# 4ch_GRT_reader_v6.net
KiCad netlist of a schematic drawn in Altium Designer
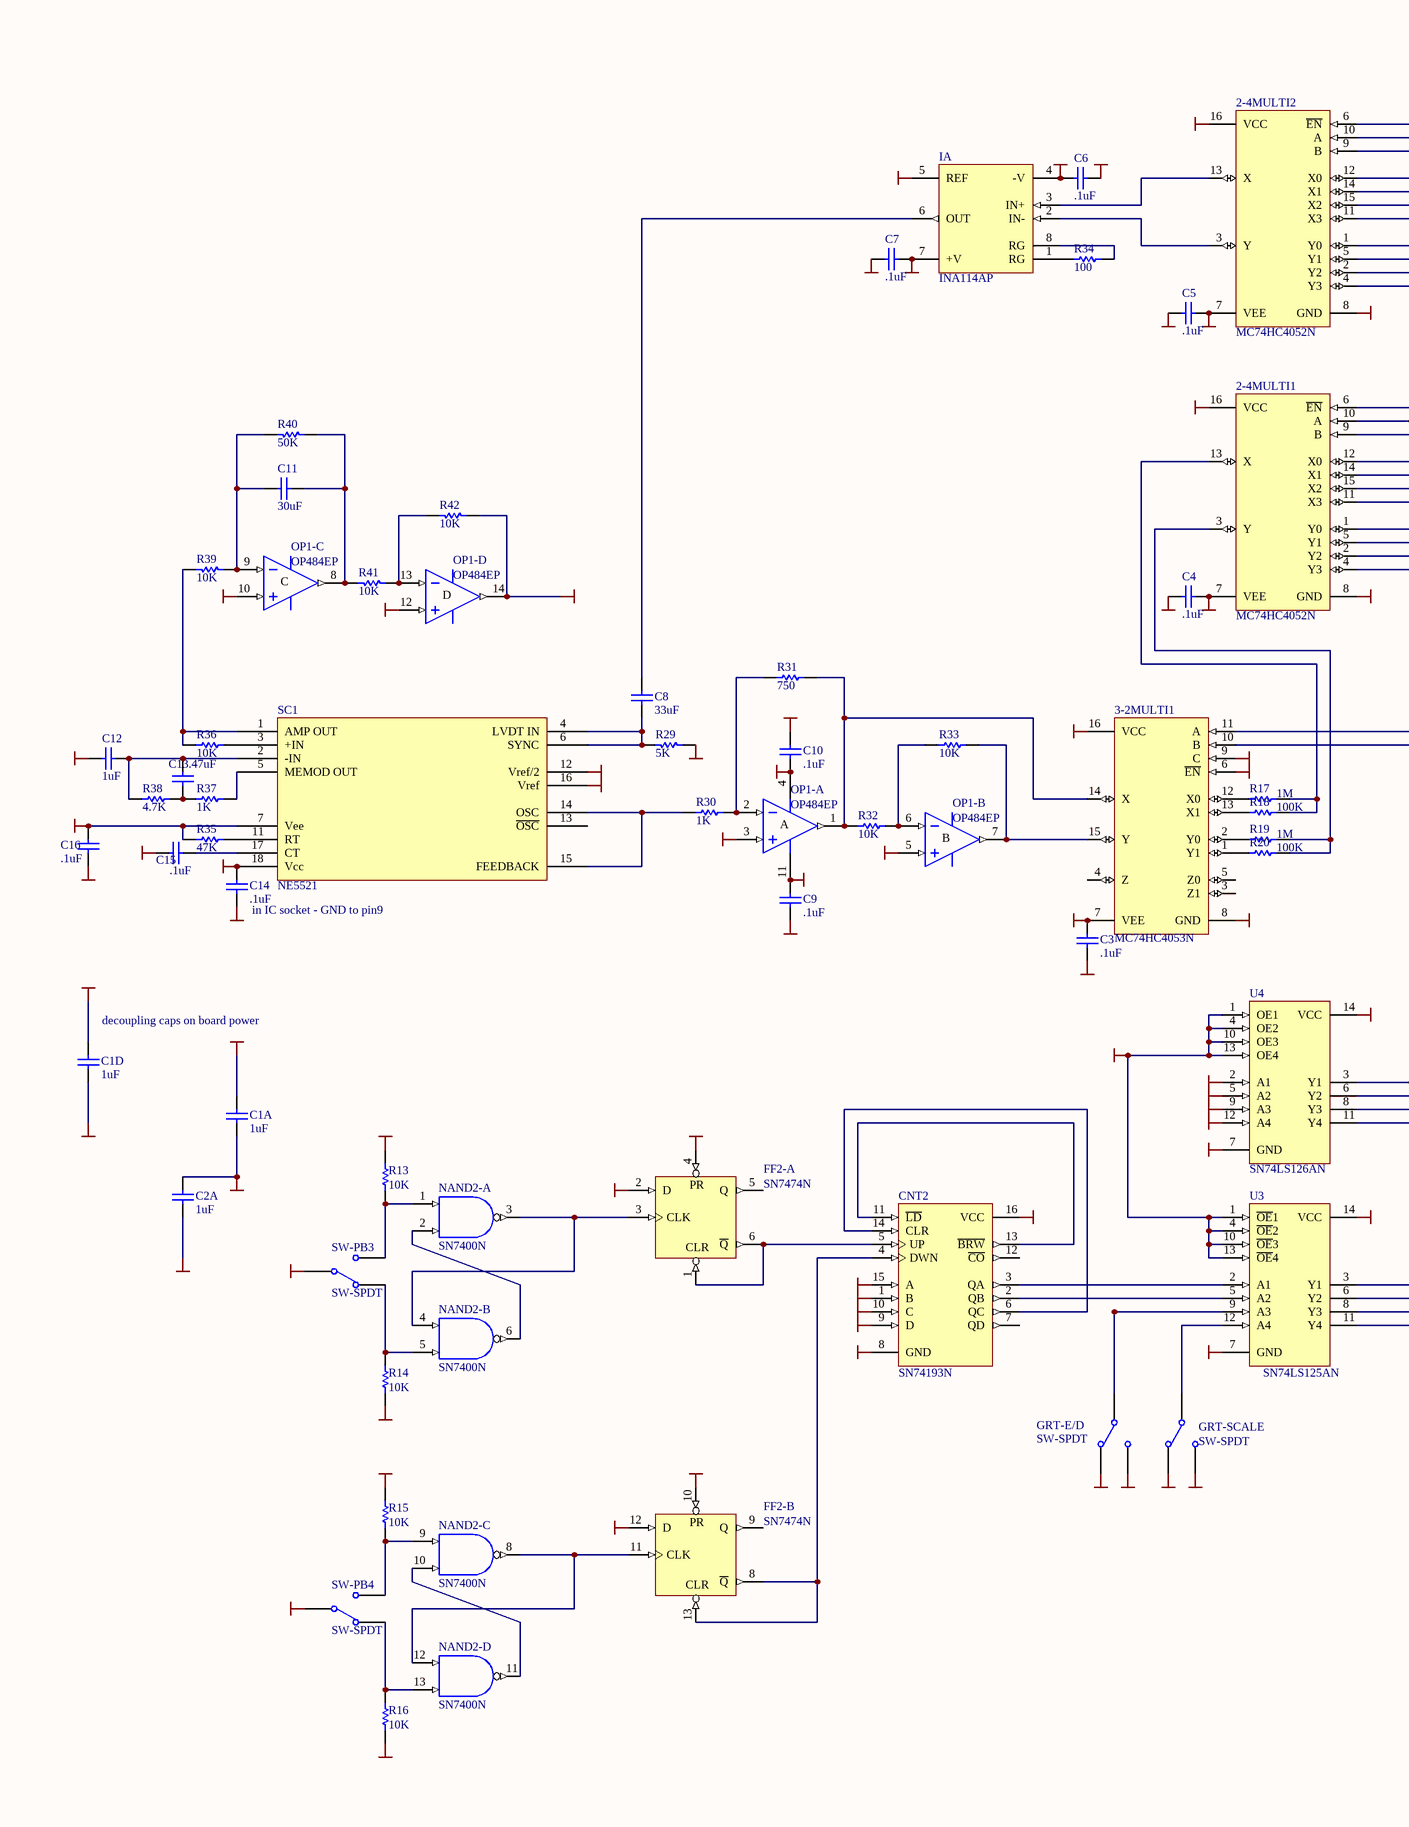
[diagram p0: 4ch GRT reader v6.SCHDOC, left]
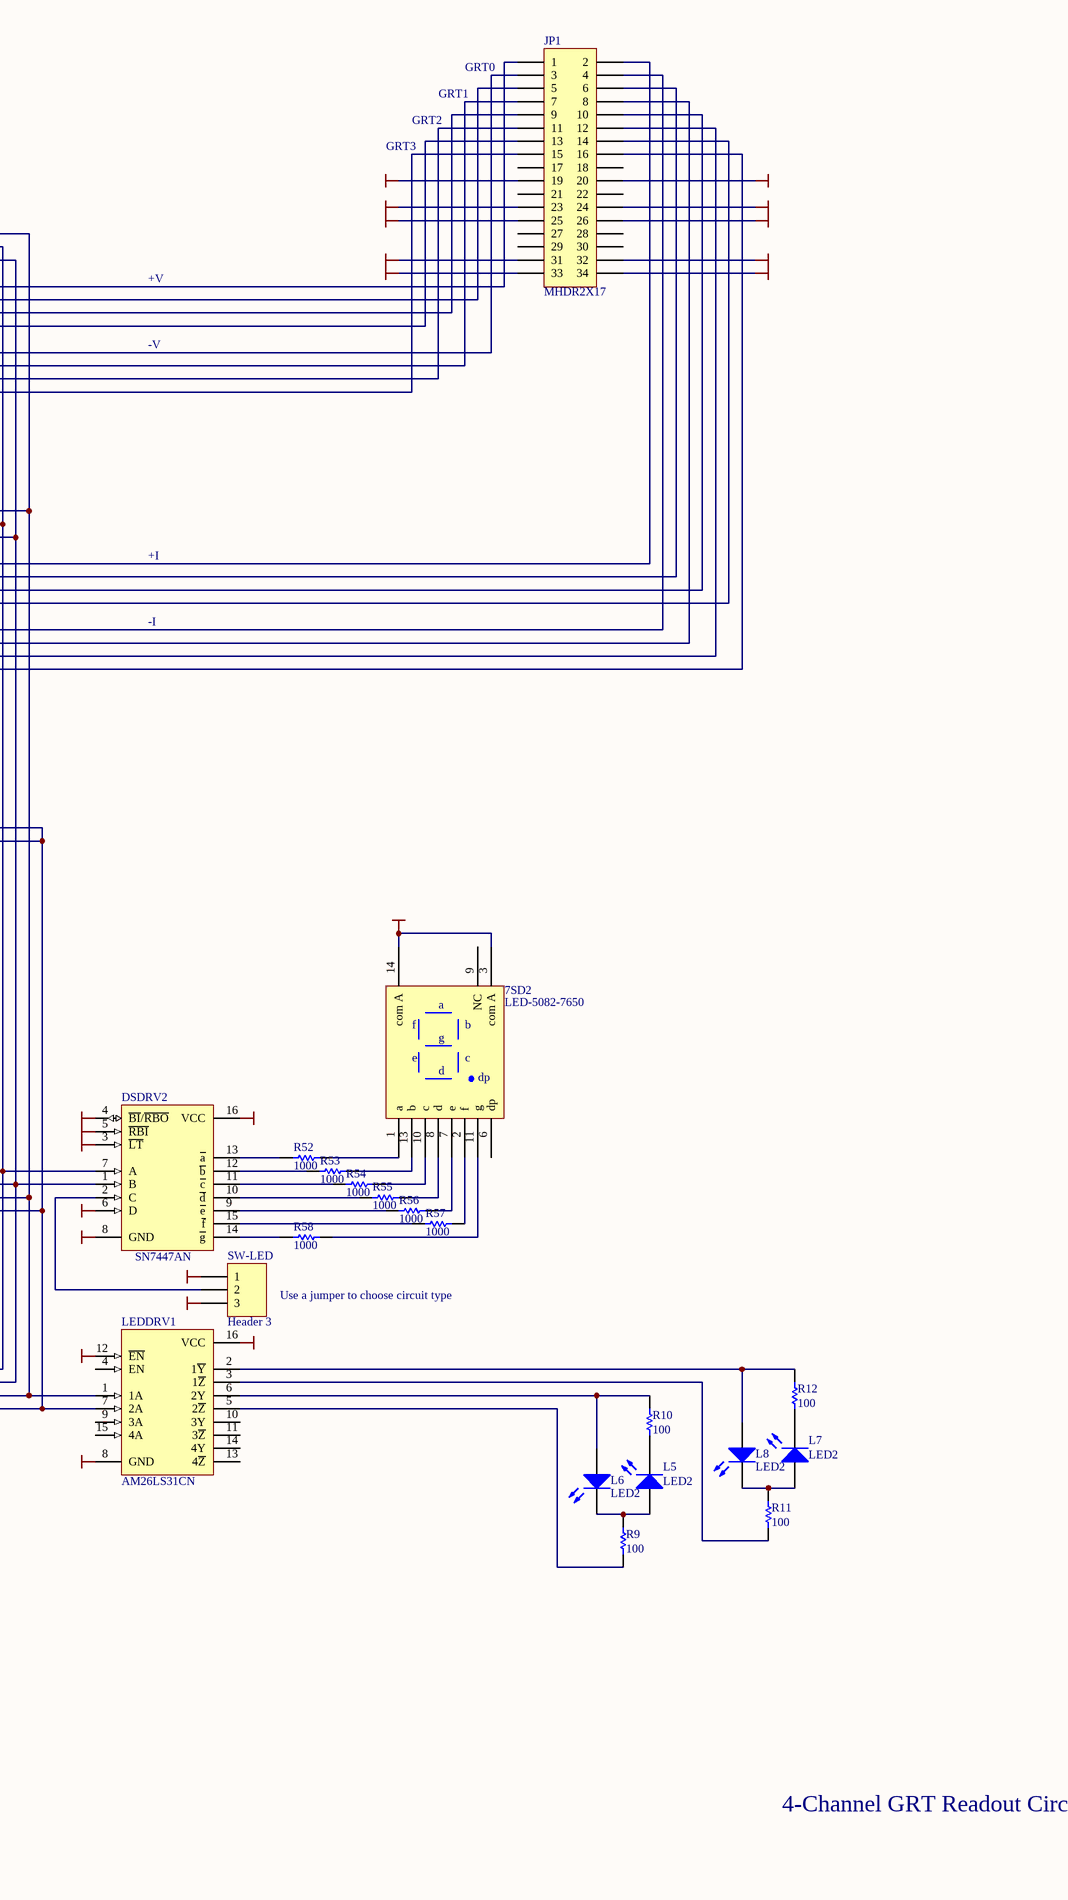
[diagram p1: 4ch GRT reader v6.SCHDOC, right]

(export (version "E")
  (design (tool "Eeschema 10.0.6"))
  (components
    (comp (ref "2-4MULTI1")
      (value "MC74HC4052N")
      (footprint "DIP-16/X1.5")
      (description "Dual 4-Channel Analog Multiplexer/Demultiplexer")
      (fields (field (name "MANUFACTURER") "ON Semiconductor") (field (name "PUBLISHER") "Altium Limited"))
      (libsource (lib "ON Semi Logic Multiplexer") (part "MC74HC4052N"))
    )
    (comp (ref "2-4MULTI2")
      (value "MC74HC4052N")
      (footprint "DIP-16/X1.5")
      (description "Dual 4-Channel Analog Multiplexer/Demultiplexer")
      (fields (field (name "MANUFACTURER") "ON Semiconductor") (field (name "PUBLISHER") "Altium Limited"))
      (libsource (lib "ON Semi Logic Multiplexer") (part "MC74HC4052N"))
    )
    (comp (ref "3-2MULTI1")
      (value "MC74HC4053N")
      (footprint "DIP-16/X1.5")
      (description "Analog Multiplexer/Demultiplexer")
      (fields (field (name "MANUFACTURER") "ON Semiconductor") (field (name "PUBLISHER") "Altium Limited"))
      (libsource (lib "ON Semi Logic Multiplexer") (part "MC74HC4053N"))
    )
    (comp (ref "7SD2")
      (value "LED-5082-7650")
      (footprint "DIP-14")
      (libsource (lib "Steves Integrated Library1") (part "LED-5082-7650"))
    )
    (comp (ref "C1A")
      (value "1uF")
      (footprint "RAD-0.2")
      (description "Capacitor")
      (fields
        (field (name "MANUFACTURER") "Generic Components")
        (field (name "ALTIUM_VALUE") "1uF")
        (field (name "PUBLISHER") "Altium Limited")
      )
      (libsource (lib "Miscellaneous Devices") (part "Cap"))
    )
    (comp (ref "C1D")
      (value "1uF")
      (footprint "RAD-0.2")
      (description "Capacitor")
      (fields
        (field (name "MANUFACTURER") "Generic Components")
        (field (name "ALTIUM_VALUE") "1uF")
        (field (name "PUBLISHER") "Altium Limited")
      )
      (libsource (lib "Miscellaneous Devices") (part "Cap"))
    )
    (comp (ref "C2A")
      (value "1uF")
      (footprint "RAD-0.2")
      (description "Capacitor")
      (fields
        (field (name "MANUFACTURER") "Generic Components")
        (field (name "ALTIUM_VALUE") "1uF")
        (field (name "PUBLISHER") "Altium Limited")
      )
      (libsource (lib "Miscellaneous Devices") (part "Cap"))
    )
    (comp (ref "C3")
      (value ".1uF")
      (footprint "RAD-0.1")
      (description "Capacitor")
      (fields
        (field (name "MANUFACTURER") "Generic Components")
        (field (name "ALTIUM_VALUE") ".1uF")
        (field (name "PUBLISHER") "Altium Limited")
      )
      (libsource (lib "Miscellaneous Devices") (part "Cap"))
    )
    (comp (ref "C4")
      (value ".1uF")
      (footprint "RAD-0.1")
      (description "Capacitor")
      (fields
        (field (name "MANUFACTURER") "Generic Components")
        (field (name "ALTIUM_VALUE") ".1uF")
        (field (name "PUBLISHER") "Altium Limited")
      )
      (libsource (lib "Miscellaneous Devices") (part "Cap"))
    )
    (comp (ref "C5")
      (value ".1uF")
      (footprint "RAD-0.1")
      (description "Capacitor")
      (fields
        (field (name "MANUFACTURER") "Generic Components")
        (field (name "ALTIUM_VALUE") ".1uF")
        (field (name "PUBLISHER") "Altium Limited")
      )
      (libsource (lib "Miscellaneous Devices") (part "Cap"))
    )
    (comp (ref "C6")
      (value ".1uF")
      (footprint "RAD-0.1")
      (description "Capacitor")
      (fields
        (field (name "MANUFACTURER") "Generic Components")
        (field (name "ALTIUM_VALUE") ".1uF")
        (field (name "PUBLISHER") "Altium Limited")
      )
      (libsource (lib "Miscellaneous Devices") (part "Cap"))
    )
    (comp (ref "C7")
      (value ".1uF")
      (footprint "RAD-0.1")
      (description "Capacitor")
      (fields
        (field (name "MANUFACTURER") "Generic Components")
        (field (name "ALTIUM_VALUE") ".1uF")
        (field (name "PUBLISHER") "Altium Limited")
      )
      (libsource (lib "Miscellaneous Devices") (part "Cap"))
    )
    (comp (ref "C8")
      (value "33uF")
      (footprint "RAD-0.1")
      (description "Capacitor")
      (fields
        (field (name "MANUFACTURER") "Generic Components")
        (field (name "ALTIUM_VALUE") "33uF")
        (field (name "PUBLISHER") "Altium Limited")
      )
      (libsource (lib "Miscellaneous Devices") (part "Cap"))
    )
    (comp (ref "C9")
      (value ".1uF")
      (footprint "RAD-0.1")
      (description "Capacitor")
      (fields
        (field (name "MANUFACTURER") "Generic Components")
        (field (name "ALTIUM_VALUE") ".1uF")
        (field (name "PUBLISHER") "Altium Limited")
      )
      (libsource (lib "Miscellaneous Devices") (part "Cap"))
    )
    (comp (ref "C10")
      (value ".1uF")
      (footprint "RAD-0.1")
      (description "Capacitor")
      (fields
        (field (name "MANUFACTURER") "Generic Components")
        (field (name "ALTIUM_VALUE") ".1uF")
        (field (name "PUBLISHER") "Altium Limited")
      )
      (libsource (lib "Miscellaneous Devices") (part "Cap"))
    )
    (comp (ref "C11")
      (value "30uF")
      (footprint "RAD-0.1")
      (description "Capacitor")
      (fields
        (field (name "MANUFACTURER") "Generic Components")
        (field (name "ALTIUM_VALUE") "30uF")
        (field (name "PUBLISHER") "Altium Limited")
      )
      (libsource (lib "Miscellaneous Devices") (part "Cap"))
    )
    (comp (ref "C12")
      (value "1uF")
      (footprint "RAD-0.1")
      (description "Capacitor")
      (fields
        (field (name "MANUFACTURER") "Generic Components")
        (field (name "ALTIUM_VALUE") "1uF")
        (field (name "PUBLISHER") "Altium Limited")
      )
      (libsource (lib "") (part "Cap_1"))
    )
    (comp (ref "C13")
      (value ".47uF")
      (footprint "RAD-0.1")
      (description "Capacitor")
      (fields
        (field (name "MANUFACTURER") "Generic Components")
        (field (name "ALTIUM_VALUE") ".47uF")
        (field (name "PUBLISHER") "Altium Limited")
      )
      (libsource (lib "Miscellaneous Devices") (part "Cap"))
    )
    (comp (ref "C14")
      (value "in IC socket - GND to pin9")
      (footprint "RAD-0.1")
      (description "Capacitor")
      (fields
        (field (name "MANUFACTURER") "Generic Components")
        (field (name "ALTIUM_VALUE") ".1uF")
        (field (name "PUBLISHER") "Altium Limited")
      )
      (libsource (lib "Miscellaneous Devices") (part "Cap"))
    )
    (comp (ref "C15")
      (value ".1uF")
      (footprint "RAD-0.1")
      (description "Capacitor")
      (fields
        (field (name "MANUFACTURER") "Generic Components")
        (field (name "ALTIUM_VALUE") ".1uF")
        (field (name "PUBLISHER") "Altium Limited")
      )
      (libsource (lib "Miscellaneous Devices") (part "Cap"))
    )
    (comp (ref "C16")
      (value ".1uF")
      (footprint "RAD-0.1")
      (description "Capacitor")
      (fields
        (field (name "MANUFACTURER") "Generic Components")
        (field (name "ALTIUM_VALUE") ".1uF")
        (field (name "PUBLISHER") "Altium Limited")
      )
      (libsource (lib "Miscellaneous Devices") (part "Cap"))
    )
    (comp (ref "CNT2")
      (value "SN74193N")
      (footprint "DIP-16/X1.5")
      (description "Synchronous 4-Bit Up/Down Counter (Dual Clock with Clear)")
      (fields (field (name "MANUFACTURER") "Texas Instruments") (field (name "PUBLISHER") "Altium Limited"))
      (libsource (lib "TI Logic Counter") (part "SN74193N"))
    )
    (comp (ref "DSDRV2")
      (value "SN7447AN")
      (footprint "DIP-16/X1.5")
      (description "BCD-to-Seven-Segment Decoder/Driver")
      (fields (field (name "MANUFACTURER") "Texas Instruments") (field (name "PUBLISHER") "Altium Limited"))
      (libsource (lib "TI Interface Display Driver") (part "SN7447AN"))
    )
    (comp (ref "FF2-")
      (value "SN7474N")
      (footprint "DIP-14/D19.7")
      (description "Dual D-Type Positive-Edge-Triggered Flip-Flop with Preset and Clear")
      (fields (field (name "MANUFACTURER") "Texas Instruments") (field (name "PUBLISHER") "Altium Limited"))
      (libsource (lib "TI Logic Flip-Flop") (part "SN7474N"))
    )
    (comp (ref "GRT-E/D")
      (value "SW-SPDT")
      (footprint "SPDT-3")
      (description "Single-Pole, Double-Throw Switch")
      (fields (field (name "MANUFACTURER") "Generic Components") (field (name "PUBLISHER") "Altium Limited"))
      (libsource (lib "Miscellaneous Devices") (part "SW-SPDT"))
    )
    (comp (ref "GRT-SCALE")
      (value "SW-SPDT")
      (footprint "SPDT-3")
      (description "Single-Pole, Double-Throw Switch")
      (fields (field (name "MANUFACTURER") "Generic Components") (field (name "PUBLISHER") "Altium Limited"))
      (libsource (lib "Miscellaneous Devices") (part "SW-SPDT"))
    )
    (comp (ref "IA")
      (value "INA114AP")
      (footprint "DIP-8")
      (description "Precision Instrumentation Amplifier")
      (fields (field (name "MANUFACTURER") "Burr-Brown") (field (name "PUBLISHER") "Altium Limited"))
      (libsource (lib "BB Instrumentation Amplifier") (part "INA114AP"))
    )
    (comp (ref "JP1")
      (value "MHDR2X17")
      (footprint "HDR2X17")
      (description "Header, 17-Pin, Dual row")
      (fields (field (name "MANUFACTURER") "Generic Components") (field (name "PUBLISHER") "Altium Limited"))
      (libsource (lib "Miscellaneous Connectors") (part "MHDR2X17"))
    )
    (comp (ref "L5")
      (value "LED2")
      (footprint "HDR1X2")
      (description "Typical RED, GREEN, YELLOW, AMBER GaAs LED")
      (fields (field (name "MANUFACTURER") "Generic Components") (field (name "PUBLISHER") "Altium Limited"))
      (libsource (lib "Miscellaneous Devices") (part "LED2"))
    )
    (comp (ref "L6")
      (value "LED2")
      (footprint "HDR1X2")
      (description "Typical RED, GREEN, YELLOW, AMBER GaAs LED")
      (fields (field (name "MANUFACTURER") "Generic Components") (field (name "PUBLISHER") "Altium Limited"))
      (libsource (lib "Miscellaneous Devices") (part "LED2"))
    )
    (comp (ref "L7")
      (value "LED2")
      (footprint "HDR1X2")
      (description "Typical RED, GREEN, YELLOW, AMBER GaAs LED")
      (fields (field (name "MANUFACTURER") "Generic Components") (field (name "PUBLISHER") "Altium Limited"))
      (libsource (lib "Miscellaneous Devices") (part "LED2"))
    )
    (comp (ref "L8")
      (value "LED2")
      (footprint "HDR1X2")
      (description "Typical RED, GREEN, YELLOW, AMBER GaAs LED")
      (fields (field (name "MANUFACTURER") "Generic Components") (field (name "PUBLISHER") "Altium Limited"))
      (libsource (lib "Miscellaneous Devices") (part "LED2"))
    )
    (comp (ref "LEDDRV1")
      (value "AM26LS31CN")
      (footprint "DIP-16/X1.5")
      (description "Quadruple Differential Line Driver")
      (fields (field (name "MANUFACTURER") "Texas Instruments") (field (name "PUBLISHER") "Altium Limited"))
      (libsource (lib "TI Interface Line Driver") (part "AM26LS31CN"))
    )
    (comp (ref "NAND2-")
      (value "SN7400N")
      (footprint "DIP-14/D19.7")
      (description "Quadruple 2-Input Positive-NAND Gate")
      (fields (field (name "MANUFACTURER") "Texas Instruments") (field (name "PUBLISHER") "Altium Limited"))
      (libsource (lib "TI Logic Gate 1") (part "SN7400N"))
    )
    (comp (ref "OP1-")
      (value "OP484EP")
      (footprint "DIP-14")
      (description "Precision Rail-to-Rail Input and Output Operational Amplifier")
      (fields (field (name "MANUFACTURER") "Analog Devices") (field (name "PUBLISHER") "Altium Limited"))
      (libsource (lib "AD Operational Amplifier") (part "OP484EP"))
    )
    (comp (ref "R9")
      (value "100")
      (footprint "AXIAL-0.3")
      (description "Resistor")
      (fields
        (field (name "MANUFACTURER") "Generic Components")
        (field (name "ALTIUM_VALUE") "100")
        (field (name "PUBLISHER") "Altium Limited")
      )
      (libsource (lib "Miscellaneous Devices") (part "Res1"))
    )
    (comp (ref "R10")
      (value "100")
      (footprint "AXIAL-0.3")
      (description "Resistor")
      (fields
        (field (name "MANUFACTURER") "Generic Components")
        (field (name "ALTIUM_VALUE") "100")
        (field (name "PUBLISHER") "Altium Limited")
      )
      (libsource (lib "Miscellaneous Devices") (part "Res1"))
    )
    (comp (ref "R11")
      (value "100")
      (footprint "AXIAL-0.3")
      (description "Resistor")
      (fields
        (field (name "MANUFACTURER") "Generic Components")
        (field (name "ALTIUM_VALUE") "100")
        (field (name "PUBLISHER") "Altium Limited")
      )
      (libsource (lib "Miscellaneous Devices") (part "Res1"))
    )
    (comp (ref "R12")
      (value "100")
      (footprint "AXIAL-0.3")
      (description "Resistor")
      (fields
        (field (name "MANUFACTURER") "Generic Components")
        (field (name "ALTIUM_VALUE") "100")
        (field (name "PUBLISHER") "Altium Limited")
      )
      (libsource (lib "Miscellaneous Devices") (part "Res1"))
    )
    (comp (ref "R13")
      (value "10K")
      (footprint "AXIAL-0.3")
      (description "Resistor")
      (fields
        (field (name "MANUFACTURER") "Generic Components")
        (field (name "ALTIUM_VALUE") "10K")
        (field (name "PUBLISHER") "Altium Limited")
      )
      (libsource (lib "Miscellaneous Devices") (part "Res1"))
    )
    (comp (ref "R14")
      (value "10K")
      (footprint "AXIAL-0.3")
      (description "Resistor")
      (fields
        (field (name "MANUFACTURER") "Generic Components")
        (field (name "ALTIUM_VALUE") "10K")
        (field (name "PUBLISHER") "Altium Limited")
      )
      (libsource (lib "Miscellaneous Devices") (part "Res1"))
    )
    (comp (ref "R15")
      (value "10K")
      (footprint "AXIAL-0.3")
      (description "Resistor")
      (fields
        (field (name "MANUFACTURER") "Generic Components")
        (field (name "ALTIUM_VALUE") "10K")
        (field (name "PUBLISHER") "Altium Limited")
      )
      (libsource (lib "Miscellaneous Devices") (part "Res1"))
    )
    (comp (ref "R16")
      (value "10K")
      (footprint "AXIAL-0.3")
      (description "Resistor")
      (fields
        (field (name "MANUFACTURER") "Generic Components")
        (field (name "ALTIUM_VALUE") "10K")
        (field (name "PUBLISHER") "Altium Limited")
      )
      (libsource (lib "Miscellaneous Devices") (part "Res1"))
    )
    (comp (ref "R17")
      (value "1M")
      (footprint "AXIAL-0.3")
      (description "Resistor")
      (fields
        (field (name "MANUFACTURER") "Generic Components")
        (field (name "ALTIUM_VALUE") "1M")
        (field (name "PUBLISHER") "Altium Limited")
      )
      (libsource (lib "Miscellaneous Devices") (part "Res1"))
    )
    (comp (ref "R18")
      (value "100K")
      (footprint "AXIAL-0.3")
      (description "Resistor")
      (fields
        (field (name "MANUFACTURER") "Generic Components")
        (field (name "ALTIUM_VALUE") "100K")
        (field (name "PUBLISHER") "Altium Limited")
      )
      (libsource (lib "Miscellaneous Devices") (part "Res1"))
    )
    (comp (ref "R19")
      (value "1M")
      (footprint "AXIAL-0.3")
      (description "Resistor")
      (fields
        (field (name "MANUFACTURER") "Generic Components")
        (field (name "ALTIUM_VALUE") "1M")
        (field (name "PUBLISHER") "Altium Limited")
      )
      (libsource (lib "Miscellaneous Devices") (part "Res1"))
    )
    (comp (ref "R20")
      (value "100K")
      (footprint "AXIAL-0.3")
      (description "Resistor")
      (fields
        (field (name "MANUFACTURER") "Generic Components")
        (field (name "ALTIUM_VALUE") "100K")
        (field (name "PUBLISHER") "Altium Limited")
      )
      (libsource (lib "Miscellaneous Devices") (part "Res1"))
    )
    (comp (ref "R29")
      (value "5K")
      (footprint "AXIAL-0.3")
      (description "Resistor")
      (fields
        (field (name "MANUFACTURER") "Generic Components")
        (field (name "ALTIUM_VALUE") "5K")
        (field (name "PUBLISHER") "Altium Limited")
      )
      (libsource (lib "") (part "Res1_2"))
    )
    (comp (ref "R30")
      (value "1K")
      (footprint "AXIAL-0.3")
      (description "Resistor")
      (fields
        (field (name "MANUFACTURER") "Generic Components")
        (field (name "ALTIUM_VALUE") "1K")
        (field (name "PUBLISHER") "Altium Limited")
      )
      (libsource (lib "Miscellaneous Devices") (part "Res1"))
    )
    (comp (ref "R31")
      (value "750")
      (footprint "AXIAL-0.3")
      (description "Resistor")
      (fields
        (field (name "MANUFACTURER") "Generic Components")
        (field (name "ALTIUM_VALUE") "750")
        (field (name "PUBLISHER") "Altium Limited")
      )
      (libsource (lib "Miscellaneous Devices") (part "Res1"))
    )
    (comp (ref "R32")
      (value "10K")
      (footprint "AXIAL-0.3")
      (description "Resistor")
      (fields
        (field (name "MANUFACTURER") "Generic Components")
        (field (name "ALTIUM_VALUE") "10K")
        (field (name "PUBLISHER") "Altium Limited")
      )
      (libsource (lib "Miscellaneous Devices") (part "Res1"))
    )
    (comp (ref "R33")
      (value "10K")
      (footprint "AXIAL-0.3")
      (description "Resistor")
      (fields
        (field (name "MANUFACTURER") "Generic Components")
        (field (name "ALTIUM_VALUE") "10K")
        (field (name "PUBLISHER") "Altium Limited")
      )
      (libsource (lib "Miscellaneous Devices") (part "Res1"))
    )
    (comp (ref "R34")
      (value "100")
      (footprint "AXIAL-0.3")
      (description "Resistor")
      (fields
        (field (name "MANUFACTURER") "Generic Components")
        (field (name "ALTIUM_VALUE") "100")
        (field (name "PUBLISHER") "Altium Limited")
      )
      (libsource (lib "Miscellaneous Devices") (part "Res1"))
    )
    (comp (ref "R35")
      (value "47K")
      (footprint "AXIAL-0.3")
      (description "Resistor")
      (fields
        (field (name "MANUFACTURER") "Generic Components")
        (field (name "ALTIUM_VALUE") "47K")
        (field (name "PUBLISHER") "Altium Limited")
      )
      (libsource (lib "Miscellaneous Devices") (part "Res1"))
    )
    (comp (ref "R36")
      (value "10K")
      (footprint "AXIAL-0.3")
      (description "Resistor")
      (fields
        (field (name "MANUFACTURER") "Generic Components")
        (field (name "ALTIUM_VALUE") "10K")
        (field (name "PUBLISHER") "Altium Limited")
      )
      (libsource (lib "") (part "Res1_1"))
    )
    (comp (ref "R37")
      (value "1K")
      (footprint "AXIAL-0.3")
      (description "Resistor")
      (fields
        (field (name "MANUFACTURER") "Generic Components")
        (field (name "ALTIUM_VALUE") "1K")
        (field (name "PUBLISHER") "Altium Limited")
      )
      (libsource (lib "") (part "Res1_1"))
    )
    (comp (ref "R38")
      (value "4.7K")
      (footprint "AXIAL-0.3")
      (description "Resistor")
      (fields
        (field (name "MANUFACTURER") "Generic Components")
        (field (name "ALTIUM_VALUE") "4.7K")
        (field (name "PUBLISHER") "Altium Limited")
      )
      (libsource (lib "") (part "Res1_1"))
    )
    (comp (ref "R39")
      (value "10K")
      (footprint "AXIAL-0.3")
      (description "Resistor")
      (fields
        (field (name "MANUFACTURER") "Generic Components")
        (field (name "ALTIUM_VALUE") "10K")
        (field (name "PUBLISHER") "Altium Limited")
      )
      (libsource (lib "") (part "Res1_1"))
    )
    (comp (ref "R40")
      (value "50K")
      (footprint "AXIAL-0.3")
      (description "Resistor")
      (fields
        (field (name "MANUFACTURER") "Generic Components")
        (field (name "ALTIUM_VALUE") "50K")
        (field (name "PUBLISHER") "Altium Limited")
      )
      (libsource (lib "") (part "Res1_1"))
    )
    (comp (ref "R41")
      (value "10K")
      (footprint "AXIAL-0.3")
      (description "Resistor")
      (fields
        (field (name "MANUFACTURER") "Generic Components")
        (field (name "ALTIUM_VALUE") "10K")
        (field (name "PUBLISHER") "Altium Limited")
      )
      (libsource (lib "") (part "Res1_1"))
    )
    (comp (ref "R42")
      (value "10K")
      (footprint "AXIAL-0.3")
      (description "Resistor")
      (fields
        (field (name "MANUFACTURER") "Generic Components")
        (field (name "ALTIUM_VALUE") "10K")
        (field (name "PUBLISHER") "Altium Limited")
      )
      (libsource (lib "") (part "Res1_1"))
    )
    (comp (ref "R52")
      (value "1000")
      (footprint "AXIAL-0.3")
      (description "Resistor")
      (fields
        (field (name "MANUFACTURER") "Generic Components")
        (field (name "ALTIUM_VALUE") "1000")
        (field (name "PUBLISHER") "Altium Limited")
      )
      (libsource (lib "Miscellaneous Devices") (part "Res1"))
    )
    (comp (ref "R53")
      (value "1000")
      (footprint "AXIAL-0.3")
      (description "Resistor")
      (fields
        (field (name "MANUFACTURER") "Generic Components")
        (field (name "ALTIUM_VALUE") "1000")
        (field (name "PUBLISHER") "Altium Limited")
      )
      (libsource (lib "Miscellaneous Devices") (part "Res1"))
    )
    (comp (ref "R54")
      (value "1000")
      (footprint "AXIAL-0.3")
      (description "Resistor")
      (fields
        (field (name "MANUFACTURER") "Generic Components")
        (field (name "ALTIUM_VALUE") "1000")
        (field (name "PUBLISHER") "Altium Limited")
      )
      (libsource (lib "Miscellaneous Devices") (part "Res1"))
    )
    (comp (ref "R55")
      (value "1000")
      (footprint "AXIAL-0.3")
      (description "Resistor")
      (fields
        (field (name "MANUFACTURER") "Generic Components")
        (field (name "ALTIUM_VALUE") "1000")
        (field (name "PUBLISHER") "Altium Limited")
      )
      (libsource (lib "Miscellaneous Devices") (part "Res1"))
    )
    (comp (ref "R56")
      (value "1000")
      (footprint "AXIAL-0.3")
      (description "Resistor")
      (fields
        (field (name "MANUFACTURER") "Generic Components")
        (field (name "ALTIUM_VALUE") "1000")
        (field (name "PUBLISHER") "Altium Limited")
      )
      (libsource (lib "Miscellaneous Devices") (part "Res1"))
    )
    (comp (ref "R57")
      (value "1000")
      (footprint "AXIAL-0.3")
      (description "Resistor")
      (fields
        (field (name "MANUFACTURER") "Generic Components")
        (field (name "ALTIUM_VALUE") "1000")
        (field (name "PUBLISHER") "Altium Limited")
      )
      (libsource (lib "Miscellaneous Devices") (part "Res1"))
    )
    (comp (ref "R58")
      (value "1000")
      (footprint "AXIAL-0.3")
      (description "Resistor")
      (fields
        (field (name "MANUFACTURER") "Generic Components")
        (field (name "ALTIUM_VALUE") "1000")
        (field (name "PUBLISHER") "Altium Limited")
      )
      (libsource (lib "Miscellaneous Devices") (part "Res1"))
    )
    (comp (ref "SC1")
      (value "NE5521")
      (footprint "DIP-18")
      (libsource (lib "Steves Integrated Library1") (part "NE5521"))
    )
    (comp (ref "SW-LED")
      (value "Header 3")
      (footprint "HDR1X3")
      (description "Header, 3-Pin")
      (fields (field (name "MANUFACTURER") "Generic Components") (field (name "PUBLISHER") "Altium Limited"))
      (libsource (lib "Miscellaneous Connectors") (part "Header 3"))
    )
    (comp (ref "SW-PB3")
      (value "SW-SPDT")
      (footprint "SPDT-3")
      (description "Single-Pole, Double-Throw Switch")
      (fields (field (name "MANUFACTURER") "Generic Components") (field (name "PUBLISHER") "Altium Limited"))
      (libsource (lib "Miscellaneous Devices") (part "SW-SPDT"))
    )
    (comp (ref "SW-PB4")
      (value "SW-SPDT")
      (footprint "SPDT-3")
      (description "Single-Pole, Double-Throw Switch")
      (fields (field (name "MANUFACTURER") "Generic Components") (field (name "PUBLISHER") "Altium Limited"))
      (libsource (lib "Miscellaneous Devices") (part "SW-SPDT"))
    )
    (comp (ref "U3")
      (value "SN74LS125AN")
      (footprint "DIP-14/D19.7")
      (description "Quadruple Bus Buffer with 3-State Outputs")
      (fields (field (name "MANUFACTURER") "Texas Instruments") (field (name "PUBLISHER") "Altium Limited"))
      (libsource (lib "TI Logic Buffer Line Driver") (part "SN74LS125AN"))
    )
    (comp (ref "U4")
      (value "SN74LS126AN")
      (footprint "DIP-14/D19.7")
      (description "Quadruple Bus Buffer with 3-State Outputs")
      (fields (field (name "MANUFACTURER") "Texas Instruments") (field (name "PUBLISHER") "Altium Limited"))
      (libsource (lib "TI Logic Buffer Line Driver") (part "SN74LS126AN"))
    )
  )
  (nets
    (net (code "1") (name "+5AV") (class "Default")
      (node (ref "2-4MULTI1") (pin "16") (pinfunction "VCC_16") (pintype "power_in"))
      (node (ref "2-4MULTI2") (pin "16") (pinfunction "VCC_16") (pintype "power_in"))
      (node (ref "3-2MULTI1") (pin "16") (pinfunction "VCC_16") (pintype "power_in"))
      (node (ref "C10") (pin "1") (pinfunction "1_1") (pintype "passive"))
      (node (ref "C14") (pin "2") (pinfunction "2_2") (pintype "passive"))
      (node (ref "C1A") (pin "2") (pinfunction "2_2") (pintype "passive"))
      (node (ref "C7") (pin "2") (pinfunction "2_2") (pintype "passive"))
      (node (ref "IA") (pin "7") (pinfunction "+V_7") (pintype "power_in"))
      (node (ref "OP1-") (pin "4") (pinfunction "V+_4") (pintype "power_in"))
      (node (ref "SC1") (pin "16") (pinfunction "Vref_16") (pintype "passive"))
      (node (ref "SC1") (pin "18") (pinfunction "Vcc_18") (pintype "passive"))
    )
    (net (code "2") (name "+5DV") (class "Default")
      (node (ref "7SD2") (pin "14") (pinfunction "com_A_14") (pintype "passive"))
      (node (ref "7SD2") (pin "3") (pinfunction "com_A_3") (pintype "passive"))
      (node (ref "C1D") (pin "2") (pinfunction "2_2") (pintype "passive"))
      (node (ref "CNT2") (pin "1") (pinfunction "B_1") (pintype "input"))
      (node (ref "CNT2") (pin "15") (pinfunction "A_15") (pintype "input"))
      (node (ref "CNT2") (pin "16") (pinfunction "VCC_16") (pintype "power_in"))
      (node (ref "DSDRV2") (pin "16") (pinfunction "VCC_16") (pintype "power_in"))
      (node (ref "DSDRV2") (pin "3") (pinfunction "~{LT}_3") (pintype "input"))
      (node (ref "DSDRV2") (pin "4") (pinfunction "~{BI}/~{RBO}_4") (pintype "bidirectional"))
      (node (ref "DSDRV2") (pin "5") (pinfunction "~{RBI}_5") (pintype "input"))
      (node (ref "FF2-") (pin "10") (pinfunction "PR_10") (pintype "input"))
      (node (ref "FF2-") (pin "12") (pinfunction "D_12") (pintype "input"))
      (node (ref "FF2-") (pin "2") (pinfunction "D_2") (pintype "input"))
      (node (ref "FF2-") (pin "4") (pinfunction "PR_4") (pintype "input"))
      (node (ref "GRT-E/D") (pin "2") (pinfunction "NC_2") (pintype "passive"))
      (node (ref "GRT-SCALE") (pin "2") (pinfunction "NC_2") (pintype "passive"))
      (node (ref "JP1") (pin "23") (pinfunction "23_23") (pintype "passive"))
      (node (ref "LEDDRV1") (pin "16") (pinfunction "VCC_16") (pintype "power_in"))
      (node (ref "R13") (pin "2") (pinfunction "2_2") (pintype "passive"))
      (node (ref "R14") (pin "1") (pinfunction "1_1") (pintype "passive"))
      (node (ref "R15") (pin "2") (pinfunction "2_2") (pintype "passive"))
      (node (ref "R16") (pin "1") (pinfunction "1_1") (pintype "passive"))
      (node (ref "SW-LED") (pin "3") (pinfunction "3_3") (pintype "passive"))
      (node (ref "U3") (pin "14") (pinfunction "VCC_14") (pintype "power_in"))
      (node (ref "U4") (pin "14") (pinfunction "VCC_14") (pintype "power_in"))
    )
    (net (code "3") (name "-5V") (class "Default")
      (node (ref "2-4MULTI1") (pin "7") (pinfunction "VEE_7") (pintype "power_in"))
      (node (ref "2-4MULTI2") (pin "7") (pinfunction "VEE_7") (pintype "power_in"))
      (node (ref "3-2MULTI1") (pin "7") (pinfunction "VEE_7") (pintype "power_in"))
      (node (ref "C16") (pin "2") (pinfunction "2_2") (pintype "passive"))
      (node (ref "C2A") (pin "1") (pinfunction "1_1") (pintype "passive"))
      (node (ref "C3") (pin "1") (pinfunction "1_1") (pintype "passive"))
      (node (ref "C4") (pin "2") (pinfunction "2_2") (pintype "passive"))
      (node (ref "C5") (pin "2") (pinfunction "2_2") (pintype "passive"))
      (node (ref "C6") (pin "1") (pinfunction "1_1") (pintype "passive"))
      (node (ref "C9") (pin "2") (pinfunction "2_2") (pintype "passive"))
      (node (ref "IA") (pin "4") (pinfunction "-V_4") (pintype "power_in"))
      (node (ref "JP1") (pin "24") (pinfunction "24_24") (pintype "passive"))
      (node (ref "OP1-") (pin "11") (pinfunction "V-_11") (pintype "power_in"))
      (node (ref "R35") (pin "2") (pinfunction "2_2") (pintype "passive"))
      (node (ref "SC1") (pin "7") (pinfunction "Vee_7") (pintype "passive"))
    )
    (net (code "4") (name "AGD") (class "Default")
      (node (ref "2-4MULTI1") (pin "8") (pinfunction "GND_8") (pintype "power_in"))
      (node (ref "2-4MULTI2") (pin "8") (pinfunction "GND_8") (pintype "power_in"))
      (node (ref "3-2MULTI1") (pin "6") (pinfunction "~{EN}_6") (pintype "input"))
      (node (ref "3-2MULTI1") (pin "8") (pinfunction "GND_8") (pintype "power_in"))
      (node (ref "3-2MULTI1") (pin "9") (pinfunction "C_9") (pintype "input"))
      (node (ref "C10") (pin "2") (pinfunction "2_2") (pintype "passive"))
      (node (ref "C12") (pin "1") (pinfunction "1_1") (pintype "passive"))
      (node (ref "C14") (pin "1") (pinfunction "1_1") (pintype "passive"))
      (node (ref "C15") (pin "1") (pinfunction "1_1") (pintype "passive"))
      (node (ref "C16") (pin "1") (pinfunction "1_1") (pintype "passive"))
      (node (ref "C1A") (pin "1") (pinfunction "1_1") (pintype "passive"))
      (node (ref "C2A") (pin "2") (pinfunction "2_2") (pintype "passive"))
      (node (ref "C3") (pin "2") (pinfunction "2_2") (pintype "passive"))
      (node (ref "C4") (pin "1") (pinfunction "1_1") (pintype "passive"))
      (node (ref "C5") (pin "1") (pinfunction "1_1") (pintype "passive"))
      (node (ref "C6") (pin "2") (pinfunction "2_2") (pintype "passive"))
      (node (ref "C7") (pin "1") (pinfunction "1_1") (pintype "passive"))
      (node (ref "C9") (pin "1") (pinfunction "1_1") (pintype "passive"))
      (node (ref "IA") (pin "5") (pinfunction "REF_5") (pintype "passive"))
      (node (ref "JP1") (pin "20") (pinfunction "20_20") (pintype "passive"))
      (node (ref "OP1-") (pin "10") (pinfunction "IN+_10") (pintype "input"))
      (node (ref "OP1-") (pin "12") (pinfunction "IN+_12") (pintype "input"))
      (node (ref "OP1-") (pin "3") (pinfunction "IN+_3") (pintype "input"))
      (node (ref "OP1-") (pin "5") (pinfunction "IN+_5") (pintype "input"))
      (node (ref "R29") (pin "2") (pinfunction "2_2") (pintype "passive"))
      (node (ref "SC1") (pin "12") (pinfunction "Vref/2_12") (pintype "passive"))
    )
    (net (code "5") (name "DGD") (class "Default")
      (node (ref "C1D") (pin "1") (pinfunction "1_1") (pintype "passive"))
      (node (ref "CNT2") (pin "10") (pinfunction "C_10") (pintype "input"))
      (node (ref "CNT2") (pin "8") (pinfunction "GND_8") (pintype "power_in"))
      (node (ref "CNT2") (pin "9") (pinfunction "D_9") (pintype "input"))
      (node (ref "DSDRV2") (pin "6") (pinfunction "D_6") (pintype "input"))
      (node (ref "DSDRV2") (pin "8") (pinfunction "GND_8") (pintype "power_in"))
      (node (ref "GRT-E/D") (pin "3") (pinfunction "NO_3") (pintype "passive"))
      (node (ref "GRT-SCALE") (pin "3") (pinfunction "NO_3") (pintype "passive"))
      (node (ref "JP1") (pin "25") (pinfunction "25_25") (pintype "passive"))
      (node (ref "LEDDRV1") (pin "12") (pinfunction "~{EN}_12") (pintype "input"))
      (node (ref "LEDDRV1") (pin "8") (pinfunction "GND_8") (pintype "power_in"))
      (node (ref "SW-LED") (pin "1") (pinfunction "1_1") (pintype "passive"))
      (node (ref "SW-PB3") (pin "1") (pinfunction "COMMON_1") (pintype "passive"))
      (node (ref "SW-PB4") (pin "1") (pinfunction "COMMON_1") (pintype "passive"))
      (node (ref "U3") (pin "7") (pinfunction "GND_7") (pintype "power_in"))
      (node (ref "U4") (pin "7") (pinfunction "GND_7") (pintype "power_in"))
    )
    (net (code "6") (name "DIO0") (class "Default")
      (node (ref "JP1") (pin "31") (pinfunction "31_31") (pintype "passive"))
      (node (ref "U4") (pin "2") (pinfunction "A1_2") (pintype "input"))
    )
    (net (code "7") (name "DIO1") (class "Default")
      (node (ref "JP1") (pin "32") (pinfunction "32_32") (pintype "passive"))
      (node (ref "U4") (pin "5") (pinfunction "A2_5") (pintype "input"))
    )
    (net (code "8") (name "DIO2") (class "Default")
      (node (ref "JP1") (pin "33") (pinfunction "33_33") (pintype "passive"))
      (node (ref "U4") (pin "9") (pinfunction "A3_9") (pintype "input"))
    )
    (net (code "9") (name "DIO3") (class "Default")
      (node (ref "JP1") (pin "34") (pinfunction "34_34") (pintype "passive"))
      (node (ref "U4") (pin "12") (pinfunction "A4_12") (pintype "input"))
    )
    (net (code "10") (name "GND") (class "Default")
      (node (ref "FF2-") (pin "7") (pinfunction "GND_7") (pintype "power_in"))
      (node (ref "NAND2-") (pin "7") (pinfunction "GND_7") (pintype "power_in"))
    )
    (net (code "11") (name "GRT OUT") (class "Default")
      (node (ref "JP1") (pin "19") (pinfunction "19_19") (pintype "passive"))
      (node (ref "OP1-") (pin "14") (pinfunction "OUT_14") (pintype "output"))
      (node (ref "R42") (pin "1") (pinfunction "1_1") (pintype "passive"))
    )
    (net (code "12") (name "L{slash}R Line") (class "Default")
      (node (ref "JP1") (pin "26") (pinfunction "26_26") (pintype "passive"))
      (node (ref "U3") (pin "1") (pinfunction "~{OE}1_1") (pintype "input"))
      (node (ref "U3") (pin "10") (pinfunction "~{OE}3_10") (pintype "input"))
      (node (ref "U3") (pin "13") (pinfunction "~{OE}4_13") (pintype "input"))
      (node (ref "U3") (pin "4") (pinfunction "~{OE}2_4") (pintype "input"))
      (node (ref "U4") (pin "1") (pinfunction "OE1_1") (pintype "input"))
      (node (ref "U4") (pin "10") (pinfunction "OE3_10") (pintype "input"))
      (node (ref "U4") (pin "13") (pinfunction "OE4_13") (pintype "input"))
      (node (ref "U4") (pin "4") (pinfunction "OE2_4") (pintype "input"))
    )
    (net (code "13") (name "Net-(2-4MULTI1-A)") (class "Default")
      (node (ref "2-4MULTI1") (pin "10") (pinfunction "A_10") (pintype "input"))
      (node (ref "2-4MULTI2") (pin "10") (pinfunction "A_10") (pintype "input"))
      (node (ref "DSDRV2") (pin "7") (pinfunction "A_7") (pintype "input"))
      (node (ref "U3") (pin "3") (pinfunction "Y1_3") (pintype "tri_state"))
      (node (ref "U4") (pin "3") (pinfunction "Y1_3") (pintype "tri_state"))
    )
    (net (code "14") (name "Net-(2-4MULTI1-B)") (class "Default")
      (node (ref "2-4MULTI1") (pin "9") (pinfunction "B_9") (pintype "input"))
      (node (ref "2-4MULTI2") (pin "9") (pinfunction "B_9") (pintype "input"))
      (node (ref "DSDRV2") (pin "1") (pinfunction "B_1") (pintype "input"))
      (node (ref "U3") (pin "6") (pinfunction "Y2_6") (pintype "tri_state"))
      (node (ref "U4") (pin "6") (pinfunction "Y2_6") (pintype "tri_state"))
    )
    (net (code "15") (name "Net-(2-4MULTI1-X)") (class "Default")
      (node (ref "2-4MULTI1") (pin "13") (pinfunction "X_13") (pintype "bidirectional"))
      (node (ref "R17") (pin "2") (pinfunction "2_2") (pintype "passive"))
      (node (ref "R18") (pin "2") (pinfunction "2_2") (pintype "passive"))
    )
    (net (code "16") (name "Net-(2-4MULTI1-X0)") (class "Default")
      (node (ref "2-4MULTI1") (pin "12") (pinfunction "X0_12") (pintype "bidirectional"))
      (node (ref "JP1") (pin "2") (pinfunction "2_2") (pintype "passive"))
    )
    (net (code "17") (name "Net-(2-4MULTI1-X1)") (class "Default")
      (node (ref "2-4MULTI1") (pin "14") (pinfunction "X1_14") (pintype "bidirectional"))
      (node (ref "JP1") (pin "6") (pinfunction "6_6") (pintype "passive"))
    )
    (net (code "18") (name "Net-(2-4MULTI1-X2)") (class "Default")
      (node (ref "2-4MULTI1") (pin "15") (pinfunction "X2_15") (pintype "bidirectional"))
      (node (ref "JP1") (pin "10") (pinfunction "10_10") (pintype "passive"))
    )
    (net (code "19") (name "Net-(2-4MULTI1-X3)") (class "Default")
      (node (ref "2-4MULTI1") (pin "11") (pinfunction "X3_11") (pintype "bidirectional"))
      (node (ref "JP1") (pin "14") (pinfunction "14_14") (pintype "passive"))
    )
    (net (code "20") (name "Net-(2-4MULTI1-Y)") (class "Default")
      (node (ref "2-4MULTI1") (pin "3") (pinfunction "Y_3") (pintype "bidirectional"))
      (node (ref "R19") (pin "2") (pinfunction "2_2") (pintype "passive"))
      (node (ref "R20") (pin "2") (pinfunction "2_2") (pintype "passive"))
    )
    (net (code "21") (name "Net-(2-4MULTI1-Y0)") (class "Default")
      (node (ref "2-4MULTI1") (pin "1") (pinfunction "Y0_1") (pintype "bidirectional"))
      (node (ref "JP1") (pin "4") (pinfunction "4_4") (pintype "passive"))
    )
    (net (code "22") (name "Net-(2-4MULTI1-Y1)") (class "Default")
      (node (ref "2-4MULTI1") (pin "5") (pinfunction "Y1_5") (pintype "bidirectional"))
      (node (ref "JP1") (pin "8") (pinfunction "8_8") (pintype "passive"))
    )
    (net (code "23") (name "Net-(2-4MULTI1-Y2)") (class "Default")
      (node (ref "2-4MULTI1") (pin "2") (pinfunction "Y2_2") (pintype "bidirectional"))
      (node (ref "JP1") (pin "12") (pinfunction "12_12") (pintype "passive"))
    )
    (net (code "24") (name "Net-(2-4MULTI1-Y3)") (class "Default")
      (node (ref "2-4MULTI1") (pin "4") (pinfunction "Y3_4") (pintype "bidirectional"))
      (node (ref "JP1") (pin "16") (pinfunction "16_16") (pintype "passive"))
    )
    (net (code "25") (name "Net-(2-4MULTI1-~{EN})") (class "Default")
      (node (ref "2-4MULTI1") (pin "6") (pinfunction "~{EN}_6") (pintype "input"))
      (node (ref "2-4MULTI2") (pin "6") (pinfunction "~{EN}_6") (pintype "input"))
      (node (ref "LEDDRV1") (pin "1") (pinfunction "1A_1") (pintype "input"))
      (node (ref "U3") (pin "8") (pinfunction "Y3_8") (pintype "tri_state"))
      (node (ref "U4") (pin "8") (pinfunction "Y3_8") (pintype "tri_state"))
    )
    (net (code "26") (name "Net-(2-4MULTI2-X)") (class "Default")
      (node (ref "2-4MULTI2") (pin "13") (pinfunction "X_13") (pintype "bidirectional"))
      (node (ref "IA") (pin "3") (pinfunction "IN+_3") (pintype "input"))
    )
    (net (code "27") (name "Net-(2-4MULTI2-X0)") (class "Default")
      (node (ref "2-4MULTI2") (pin "12") (pinfunction "X0_12") (pintype "bidirectional"))
      (node (ref "JP1") (pin "1") (pinfunction "1_1") (pintype "passive"))
    )
    (net (code "28") (name "Net-(2-4MULTI2-X1)") (class "Default")
      (node (ref "2-4MULTI2") (pin "14") (pinfunction "X1_14") (pintype "bidirectional"))
      (node (ref "JP1") (pin "5") (pinfunction "5_5") (pintype "passive"))
    )
    (net (code "29") (name "Net-(2-4MULTI2-X2)") (class "Default")
      (node (ref "2-4MULTI2") (pin "15") (pinfunction "X2_15") (pintype "bidirectional"))
      (node (ref "JP1") (pin "9") (pinfunction "9_9") (pintype "passive"))
    )
    (net (code "30") (name "Net-(2-4MULTI2-X3)") (class "Default")
      (node (ref "2-4MULTI2") (pin "11") (pinfunction "X3_11") (pintype "bidirectional"))
      (node (ref "JP1") (pin "13") (pinfunction "13_13") (pintype "passive"))
    )
    (net (code "31") (name "Net-(2-4MULTI2-Y)") (class "Default")
      (node (ref "2-4MULTI2") (pin "3") (pinfunction "Y_3") (pintype "bidirectional"))
      (node (ref "IA") (pin "2") (pinfunction "IN-_2") (pintype "input"))
    )
    (net (code "32") (name "Net-(2-4MULTI2-Y0)") (class "Default")
      (node (ref "2-4MULTI2") (pin "1") (pinfunction "Y0_1") (pintype "bidirectional"))
      (node (ref "JP1") (pin "3") (pinfunction "3_3") (pintype "passive"))
    )
    (net (code "33") (name "Net-(2-4MULTI2-Y1)") (class "Default")
      (node (ref "2-4MULTI2") (pin "5") (pinfunction "Y1_5") (pintype "bidirectional"))
      (node (ref "JP1") (pin "7") (pinfunction "7_7") (pintype "passive"))
    )
    (net (code "34") (name "Net-(2-4MULTI2-Y2)") (class "Default")
      (node (ref "2-4MULTI2") (pin "2") (pinfunction "Y2_2") (pintype "bidirectional"))
      (node (ref "JP1") (pin "11") (pinfunction "11_11") (pintype "passive"))
    )
    (net (code "35") (name "Net-(2-4MULTI2-Y3)") (class "Default")
      (node (ref "2-4MULTI2") (pin "4") (pinfunction "Y3_4") (pintype "bidirectional"))
      (node (ref "JP1") (pin "15") (pinfunction "15_15") (pintype "passive"))
    )
    (net (code "36") (name "Net-(3-2MULTI1-A)") (class "Default")
      (node (ref "3-2MULTI1") (pin "10") (pinfunction "B_10") (pintype "input"))
      (node (ref "3-2MULTI1") (pin "11") (pinfunction "A_11") (pintype "input"))
      (node (ref "LEDDRV1") (pin "7") (pinfunction "2A_7") (pintype "input"))
      (node (ref "U3") (pin "11") (pinfunction "Y4_11") (pintype "tri_state"))
      (node (ref "U4") (pin "11") (pinfunction "Y4_11") (pintype "tri_state"))
    )
    (net (code "37") (name "Net-(3-2MULTI1-X)") (class "Default")
      (node (ref "3-2MULTI1") (pin "14") (pinfunction "X_14") (pintype "bidirectional"))
      (node (ref "OP1-") (pin "1") (pinfunction "OUT_1") (pintype "output"))
      (node (ref "R31") (pin "2") (pinfunction "2_2") (pintype "passive"))
      (node (ref "R32") (pin "1") (pinfunction "1_1") (pintype "passive"))
    )
    (net (code "38") (name "Net-(3-2MULTI1-X0)") (class "Default")
      (node (ref "3-2MULTI1") (pin "12") (pinfunction "X0_12") (pintype "bidirectional"))
      (node (ref "R17") (pin "1") (pinfunction "1_1") (pintype "passive"))
    )
    (net (code "39") (name "Net-(3-2MULTI1-X1)") (class "Default")
      (node (ref "3-2MULTI1") (pin "13") (pinfunction "X1_13") (pintype "bidirectional"))
      (node (ref "R18") (pin "1") (pinfunction "1_1") (pintype "passive"))
    )
    (net (code "40") (name "Net-(3-2MULTI1-Y)") (class "Default")
      (node (ref "3-2MULTI1") (pin "15") (pinfunction "Y_15") (pintype "bidirectional"))
      (node (ref "OP1-") (pin "7") (pinfunction "OUT_7") (pintype "output"))
      (node (ref "R33") (pin "2") (pinfunction "2_2") (pintype "passive"))
    )
    (net (code "41") (name "Net-(3-2MULTI1-Y0)") (class "Default")
      (node (ref "3-2MULTI1") (pin "2") (pinfunction "Y0_2") (pintype "bidirectional"))
      (node (ref "R19") (pin "1") (pinfunction "1_1") (pintype "passive"))
    )
    (net (code "42") (name "Net-(3-2MULTI1-Y1)") (class "Default")
      (node (ref "3-2MULTI1") (pin "1") (pinfunction "Y1_1") (pintype "bidirectional"))
      (node (ref "R20") (pin "1") (pinfunction "1_1") (pintype "passive"))
    )
    (net (code "43") (name "Net-(7SD2-a)") (class "Default")
      (node (ref "7SD2") (pin "1") (pinfunction "a_1") (pintype "passive"))
      (node (ref "R52") (pin "2") (pinfunction "2_2") (pintype "passive"))
    )
    (net (code "44") (name "Net-(7SD2-b)") (class "Default")
      (node (ref "7SD2") (pin "13") (pinfunction "b_13") (pintype "passive"))
      (node (ref "R53") (pin "2") (pinfunction "2_2") (pintype "passive"))
    )
    (net (code "45") (name "Net-(7SD2-c)") (class "Default")
      (node (ref "7SD2") (pin "10") (pinfunction "c_10") (pintype "passive"))
      (node (ref "R54") (pin "2") (pinfunction "2_2") (pintype "passive"))
    )
    (net (code "46") (name "Net-(7SD2-d)") (class "Default")
      (node (ref "7SD2") (pin "8") (pinfunction "d_8") (pintype "passive"))
      (node (ref "R55") (pin "2") (pinfunction "2_2") (pintype "passive"))
    )
    (net (code "47") (name "Net-(7SD2-e)") (class "Default")
      (node (ref "7SD2") (pin "7") (pinfunction "e_7") (pintype "passive"))
      (node (ref "R56") (pin "2") (pinfunction "2_2") (pintype "passive"))
    )
    (net (code "48") (name "Net-(7SD2-f)") (class "Default")
      (node (ref "7SD2") (pin "2") (pinfunction "f_2") (pintype "passive"))
      (node (ref "R57") (pin "2") (pinfunction "2_2") (pintype "passive"))
    )
    (net (code "49") (name "Net-(7SD2-g)") (class "Default")
      (node (ref "7SD2") (pin "11") (pinfunction "g_11") (pintype "passive"))
      (node (ref "R58") (pin "2") (pinfunction "2_2") (pintype "passive"))
    )
    (net (code "50") (name "Net-(C13-Pad1)") (class "Default")
      (node (ref "C13") (pin "1") (pinfunction "1_1") (pintype "passive"))
      (node (ref "R37") (pin "2") (pinfunction "2_2") (pintype "passive"))
      (node (ref "R38") (pin "1") (pinfunction "1_1") (pintype "passive"))
    )
    (net (code "51") (name "Net-(CNT2-CLR)") (class "Default")
      (node (ref "CNT2") (pin "14") (pinfunction "CLR_14") (pintype "input"))
      (node (ref "CNT2") (pin "6") (pinfunction "QC_6") (pintype "output"))
    )
    (net (code "52") (name "Net-(CNT2-DWN)") (class "Default")
      (node (ref "CNT2") (pin "4") (pinfunction "DWN_4") (pintype "input"))
      (node (ref "FF2-") (pin "13") (pinfunction "CLR_13") (pintype "input"))
      (node (ref "FF2-") (pin "8") (pinfunction "~{Q}_8") (pintype "output"))
    )
    (net (code "53") (name "Net-(CNT2-QA)") (class "Default")
      (node (ref "CNT2") (pin "3") (pinfunction "QA_3") (pintype "output"))
      (node (ref "U3") (pin "2") (pinfunction "A1_2") (pintype "input"))
    )
    (net (code "54") (name "Net-(CNT2-QB)") (class "Default")
      (node (ref "CNT2") (pin "2") (pinfunction "QB_2") (pintype "output"))
      (node (ref "U3") (pin "5") (pinfunction "A2_5") (pintype "input"))
    )
    (net (code "55") (name "Net-(CNT2-UP)") (class "Default")
      (node (ref "CNT2") (pin "5") (pinfunction "UP_5") (pintype "input"))
      (node (ref "FF2-") (pin "1") (pinfunction "CLR_1") (pintype "input"))
      (node (ref "FF2-") (pin "6") (pinfunction "~{Q}_6") (pintype "output"))
    )
    (net (code "56") (name "Net-(CNT2-~{BRW})") (class "Default")
      (node (ref "CNT2") (pin "11") (pinfunction "~{LD}_11") (pintype "input"))
      (node (ref "CNT2") (pin "13") (pinfunction "~{BRW}_13") (pintype "output"))
    )
    (net (code "57") (name "Net-(DSDRV2-C)") (class "Default")
      (node (ref "DSDRV2") (pin "2") (pinfunction "C_2") (pintype "input"))
      (node (ref "SW-LED") (pin "2") (pinfunction "2_2") (pintype "passive"))
    )
    (net (code "58") (name "Net-(DSDRV2-~{a})") (class "Default")
      (node (ref "DSDRV2") (pin "13") (pinfunction "~{a}_13") (pintype "open_collector"))
      (node (ref "R52") (pin "1") (pinfunction "1_1") (pintype "passive"))
    )
    (net (code "59") (name "Net-(DSDRV2-~{b})") (class "Default")
      (node (ref "DSDRV2") (pin "12") (pinfunction "~{b}_12") (pintype "open_collector"))
      (node (ref "R53") (pin "1") (pinfunction "1_1") (pintype "passive"))
    )
    (net (code "60") (name "Net-(DSDRV2-~{c})") (class "Default")
      (node (ref "DSDRV2") (pin "11") (pinfunction "~{c}_11") (pintype "open_collector"))
      (node (ref "R54") (pin "1") (pinfunction "1_1") (pintype "passive"))
    )
    (net (code "61") (name "Net-(DSDRV2-~{d})") (class "Default")
      (node (ref "DSDRV2") (pin "10") (pinfunction "~{d}_10") (pintype "open_collector"))
      (node (ref "R55") (pin "1") (pinfunction "1_1") (pintype "passive"))
    )
    (net (code "62") (name "Net-(DSDRV2-~{e})") (class "Default")
      (node (ref "DSDRV2") (pin "9") (pinfunction "~{e}_9") (pintype "open_collector"))
      (node (ref "R56") (pin "1") (pinfunction "1_1") (pintype "passive"))
    )
    (net (code "63") (name "Net-(DSDRV2-~{f})") (class "Default")
      (node (ref "DSDRV2") (pin "15") (pinfunction "~{f}_15") (pintype "open_collector"))
      (node (ref "R57") (pin "1") (pinfunction "1_1") (pintype "passive"))
    )
    (net (code "64") (name "Net-(DSDRV2-~{g})") (class "Default")
      (node (ref "DSDRV2") (pin "14") (pinfunction "~{g}_14") (pintype "open_collector"))
      (node (ref "R58") (pin "1") (pinfunction "1_1") (pintype "passive"))
    )
    (net (code "65") (name "Net-(FF2-A-CLK)") (class "Default")
      (node (ref "FF2-") (pin "3") (pinfunction "CLK_3") (pintype "input"))
      (node (ref "NAND2-") (pin "3") (pinfunction "Y_3") (pintype "output"))
      (node (ref "NAND2-") (pin "4") (pinfunction "A_4") (pintype "input"))
    )
    (net (code "66") (name "Net-(FF2-B-CLK)") (class "Default")
      (node (ref "FF2-") (pin "11") (pinfunction "CLK_11") (pintype "input"))
      (node (ref "NAND2-") (pin "12") (pinfunction "A_12") (pintype "input"))
      (node (ref "NAND2-") (pin "8") (pinfunction "Y_8") (pintype "output"))
    )
    (net (code "67") (name "Net-(GRT-E/D-COMMON)") (class "Default")
      (node (ref "GRT-E/D") (pin "1") (pinfunction "COMMON_1") (pintype "passive"))
      (node (ref "U3") (pin "9") (pinfunction "A3_9") (pintype "input"))
    )
    (net (code "68") (name "Net-(GRT-SCALE-COMMON)") (class "Default")
      (node (ref "GRT-SCALE") (pin "1") (pinfunction "COMMON_1") (pintype "passive"))
      (node (ref "U3") (pin "12") (pinfunction "A4_12") (pintype "input"))
    )
    (net (code "69") (name "Net-(IA-OUT)") (class "Default")
      (node (ref "C8") (pin "2") (pinfunction "2_2") (pintype "passive"))
      (node (ref "IA") (pin "6") (pinfunction "OUT_6") (pintype "output"))
    )
    (net (code "70") (name "Net-(IA-RG-Pad1)") (class "Default")
      (node (ref "IA") (pin "1") (pinfunction "RG_1") (pintype "passive"))
      (node (ref "R34") (pin "2") (pinfunction "2_2") (pintype "passive"))
    )
    (net (code "71") (name "Net-(IA-RG-Pad8)") (class "Default")
      (node (ref "IA") (pin "8") (pinfunction "RG_8") (pintype "passive"))
      (node (ref "R34") (pin "1") (pinfunction "1_1") (pintype "passive"))
    )
    (net (code "72") (name "Net-(L5-A)") (class "Default")
      (node (ref "L5") (pin "1") (pinfunction "A_1") (pintype "passive"))
      (node (ref "L6") (pin "2") (pinfunction "K_2") (pintype "passive"))
      (node (ref "R9") (pin "2") (pinfunction "2_2") (pintype "passive"))
    )
    (net (code "73") (name "Net-(L5-K)") (class "Default")
      (node (ref "L5") (pin "2") (pinfunction "K_2") (pintype "passive"))
      (node (ref "R10") (pin "1") (pinfunction "1_1") (pintype "passive"))
    )
    (net (code "74") (name "Net-(L6-A)") (class "Default")
      (node (ref "L6") (pin "1") (pinfunction "A_1") (pintype "passive"))
      (node (ref "LEDDRV1") (pin "6") (pinfunction "2Y_6") (pintype "tri_state"))
      (node (ref "R10") (pin "2") (pinfunction "2_2") (pintype "passive"))
    )
    (net (code "75") (name "Net-(L7-A)") (class "Default")
      (node (ref "L7") (pin "1") (pinfunction "A_1") (pintype "passive"))
      (node (ref "L8") (pin "2") (pinfunction "K_2") (pintype "passive"))
      (node (ref "R11") (pin "2") (pinfunction "2_2") (pintype "passive"))
    )
    (net (code "76") (name "Net-(L7-K)") (class "Default")
      (node (ref "L7") (pin "2") (pinfunction "K_2") (pintype "passive"))
      (node (ref "R12") (pin "1") (pinfunction "1_1") (pintype "passive"))
    )
    (net (code "77") (name "Net-(L8-A)") (class "Default")
      (node (ref "L8") (pin "1") (pinfunction "A_1") (pintype "passive"))
      (node (ref "LEDDRV1") (pin "2") (pinfunction "1~{Y}_2") (pintype "tri_state"))
      (node (ref "R12") (pin "2") (pinfunction "2_2") (pintype "passive"))
    )
    (net (code "78") (name "Net-(LEDDRV1-1~{Z})") (class "Default")
      (node (ref "LEDDRV1") (pin "3") (pinfunction "1~{Z}_3") (pintype "tri_state"))
      (node (ref "R11") (pin "1") (pinfunction "1_1") (pintype "passive"))
    )
    (net (code "79") (name "Net-(LEDDRV1-2~{Z})") (class "Default")
      (node (ref "LEDDRV1") (pin "5") (pinfunction "2~{Z}_5") (pintype "tri_state"))
      (node (ref "R9") (pin "1") (pinfunction "1_1") (pintype "passive"))
    )
    (net (code "80") (name "Net-(NAND2-A-A)") (class "Default")
      (node (ref "NAND2-") (pin "1") (pinfunction "A_1") (pintype "input"))
      (node (ref "R13") (pin "1") (pinfunction "1_1") (pintype "passive"))
      (node (ref "SW-PB3") (pin "3") (pinfunction "NO_3") (pintype "passive"))
    )
    (net (code "81") (name "Net-(NAND2-A-B)") (class "Default")
      (node (ref "NAND2-") (pin "2") (pinfunction "B_2") (pintype "input"))
      (node (ref "NAND2-") (pin "6") (pinfunction "Y_6") (pintype "output"))
    )
    (net (code "82") (name "Net-(NAND2-B-B)") (class "Default")
      (node (ref "NAND2-") (pin "5") (pinfunction "B_5") (pintype "input"))
      (node (ref "R14") (pin "2") (pinfunction "2_2") (pintype "passive"))
      (node (ref "SW-PB3") (pin "2") (pinfunction "NC_2") (pintype "passive"))
    )
    (net (code "83") (name "Net-(NAND2-C-A)") (class "Default")
      (node (ref "NAND2-") (pin "9") (pinfunction "A_9") (pintype "input"))
      (node (ref "R15") (pin "1") (pinfunction "1_1") (pintype "passive"))
      (node (ref "SW-PB4") (pin "3") (pinfunction "NO_3") (pintype "passive"))
    )
    (net (code "84") (name "Net-(NAND2-C-B)") (class "Default")
      (node (ref "NAND2-") (pin "10") (pinfunction "B_10") (pintype "input"))
      (node (ref "NAND2-") (pin "11") (pinfunction "Y_11") (pintype "output"))
    )
    (net (code "85") (name "Net-(NAND2-D-B)") (class "Default")
      (node (ref "NAND2-") (pin "13") (pinfunction "B_13") (pintype "input"))
      (node (ref "R16") (pin "2") (pinfunction "2_2") (pintype "passive"))
      (node (ref "SW-PB4") (pin "2") (pinfunction "NC_2") (pintype "passive"))
    )
    (net (code "86") (name "Net-(OP1-A-IN-)") (class "Default")
      (node (ref "OP1-") (pin "2") (pinfunction "IN-_2") (pintype "input"))
      (node (ref "R30") (pin "2") (pinfunction "2_2") (pintype "passive"))
      (node (ref "R31") (pin "1") (pinfunction "1_1") (pintype "passive"))
    )
    (net (code "87") (name "Net-(OP1-B-IN-)") (class "Default")
      (node (ref "OP1-") (pin "6") (pinfunction "IN-_6") (pintype "input"))
      (node (ref "R32") (pin "2") (pinfunction "2_2") (pintype "passive"))
      (node (ref "R33") (pin "1") (pinfunction "1_1") (pintype "passive"))
    )
    (net (code "88") (name "Net-(OP1-C-IN-)") (class "Default")
      (node (ref "C11") (pin "1") (pinfunction "1_1") (pintype "passive"))
      (node (ref "OP1-") (pin "9") (pinfunction "IN-_9") (pintype "input"))
      (node (ref "R39") (pin "1") (pinfunction "1_1") (pintype "passive"))
      (node (ref "R40") (pin "2") (pinfunction "2_2") (pintype "passive"))
    )
    (net (code "89") (name "Net-(OP1-C-OUT)") (class "Default")
      (node (ref "C11") (pin "2") (pinfunction "2_2") (pintype "passive"))
      (node (ref "OP1-") (pin "8") (pinfunction "OUT_8") (pintype "output"))
      (node (ref "R40") (pin "1") (pinfunction "1_1") (pintype "passive"))
      (node (ref "R41") (pin "2") (pinfunction "2_2") (pintype "passive"))
    )
    (net (code "90") (name "Net-(OP1-D-IN-)") (class "Default")
      (node (ref "OP1-") (pin "13") (pinfunction "IN-_13") (pintype "input"))
      (node (ref "R41") (pin "1") (pinfunction "1_1") (pintype "passive"))
      (node (ref "R42") (pin "2") (pinfunction "2_2") (pintype "passive"))
    )
    (net (code "91") (name "Net-(SC1-+IN)") (class "Default")
      (node (ref "R36") (pin "1") (pinfunction "1_1") (pintype "passive"))
      (node (ref "SC1") (pin "3") (pinfunction "+IN_3") (pintype "passive"))
    )
    (net (code "92") (name "Net-(SC1--IN)") (class "Default")
      (node (ref "C12") (pin "2") (pinfunction "2_2") (pintype "passive"))
      (node (ref "C13") (pin "2") (pinfunction "2_2") (pintype "passive"))
      (node (ref "R38") (pin "2") (pinfunction "2_2") (pintype "passive"))
      (node (ref "SC1") (pin "2") (pinfunction "-IN_2") (pintype "passive"))
    )
    (net (code "93") (name "Net-(SC1-AMP_OUT)") (class "Default")
      (node (ref "R36") (pin "2") (pinfunction "2_2") (pintype "passive"))
      (node (ref "R39") (pin "2") (pinfunction "2_2") (pintype "passive"))
      (node (ref "SC1") (pin "1") (pinfunction "AMP_OUT_1") (pintype "passive"))
    )
    (net (code "94") (name "Net-(SC1-CT)") (class "Default")
      (node (ref "C15") (pin "2") (pinfunction "2_2") (pintype "passive"))
      (node (ref "SC1") (pin "17") (pinfunction "CT_17") (pintype "passive"))
    )
    (net (code "95") (name "Net-(SC1-FEEDBACK)") (class "Default")
      (node (ref "R30") (pin "1") (pinfunction "1_1") (pintype "passive"))
      (node (ref "SC1") (pin "14") (pinfunction "OSC_14") (pintype "passive"))
      (node (ref "SC1") (pin "15") (pinfunction "FEEDBACK_15") (pintype "passive"))
    )
    (net (code "96") (name "Net-(SC1-LVDT_IN)") (class "Default")
      (node (ref "C8") (pin "1") (pinfunction "1_1") (pintype "passive"))
      (node (ref "R29") (pin "1") (pinfunction "1_1") (pintype "passive"))
      (node (ref "SC1") (pin "4") (pinfunction "LVDT_IN_4") (pintype "passive"))
      (node (ref "SC1") (pin "6") (pinfunction "SYNC_6") (pintype "passive"))
    )
    (net (code "97") (name "Net-(SC1-MEMOD_OUT)") (class "Default")
      (node (ref "R37") (pin "1") (pinfunction "1_1") (pintype "passive"))
      (node (ref "SC1") (pin "5") (pinfunction "MEMOD_OUT_5") (pintype "passive"))
    )
    (net (code "98") (name "Net-(SC1-RT)") (class "Default")
      (node (ref "R35") (pin "1") (pinfunction "1_1") (pintype "passive"))
      (node (ref "SC1") (pin "11") (pinfunction "RT_11") (pintype "passive"))
    )
    (net (code "99") (name "VCC") (class "Default")
      (node (ref "FF2-") (pin "14") (pinfunction "VCC_14") (pintype "power_in"))
      (node (ref "NAND2-") (pin "14") (pinfunction "VCC_14") (pintype "power_in"))
    )
    (net (code "100") (name "unconnected-(3-2MULTI1-Z-Pad4)") (class "Default")
      (node (ref "3-2MULTI1") (pin "4") (pinfunction "Z_4") (pintype "bidirectional"))
    )
    (net (code "101") (name "unconnected-(3-2MULTI1-Z0-Pad5)") (class "Default")
      (node (ref "3-2MULTI1") (pin "5") (pinfunction "Z0_5") (pintype "bidirectional"))
    )
    (net (code "102") (name "unconnected-(3-2MULTI1-Z1-Pad3)") (class "Default")
      (node (ref "3-2MULTI1") (pin "3") (pinfunction "Z1_3") (pintype "bidirectional"))
    )
    (net (code "103") (name "unconnected-(7SD2-NC-Pad9)") (class "Default")
      (node (ref "7SD2") (pin "9") (pinfunction "NC_9") (pintype "passive"))
    )
    (net (code "104") (name "unconnected-(7SD2-dp-Pad6)") (class "Default")
      (node (ref "7SD2") (pin "6") (pinfunction "dp_6") (pintype "passive"))
    )
    (net (code "105") (name "unconnected-(CNT2-QD-Pad7)") (class "Default")
      (node (ref "CNT2") (pin "7") (pinfunction "QD_7") (pintype "output"))
    )
    (net (code "106") (name "unconnected-(CNT2-~{CO}-Pad12)") (class "Default")
      (node (ref "CNT2") (pin "12") (pinfunction "~{CO}_12") (pintype "output"))
    )
    (net (code "107") (name "unconnected-(FF2-A-Q-Pad5)") (class "Default")
      (node (ref "FF2-") (pin "5") (pinfunction "Q_5") (pintype "output"))
    )
    (net (code "108") (name "unconnected-(FF2-B-Q-Pad9)") (class "Default")
      (node (ref "FF2-") (pin "9") (pinfunction "Q_9") (pintype "output"))
    )
    (net (code "109") (name "unconnected-(JP1-Pad17)") (class "Default")
      (node (ref "JP1") (pin "17") (pinfunction "17_17") (pintype "passive"))
    )
    (net (code "110") (name "unconnected-(JP1-Pad18)") (class "Default")
      (node (ref "JP1") (pin "18") (pinfunction "18_18") (pintype "passive"))
    )
    (net (code "111") (name "unconnected-(JP1-Pad21)") (class "Default")
      (node (ref "JP1") (pin "21") (pinfunction "21_21") (pintype "passive"))
    )
    (net (code "112") (name "unconnected-(JP1-Pad22)") (class "Default")
      (node (ref "JP1") (pin "22") (pinfunction "22_22") (pintype "passive"))
    )
    (net (code "113") (name "unconnected-(JP1-Pad27)") (class "Default")
      (node (ref "JP1") (pin "27") (pinfunction "27_27") (pintype "passive"))
    )
    (net (code "114") (name "unconnected-(JP1-Pad28)") (class "Default")
      (node (ref "JP1") (pin "28") (pinfunction "28_28") (pintype "passive"))
    )
    (net (code "115") (name "unconnected-(JP1-Pad29)") (class "Default")
      (node (ref "JP1") (pin "29") (pinfunction "29_29") (pintype "passive"))
    )
    (net (code "116") (name "unconnected-(JP1-Pad30)") (class "Default")
      (node (ref "JP1") (pin "30") (pinfunction "30_30") (pintype "passive"))
    )
    (net (code "117") (name "unconnected-(LEDDRV1-3A-Pad9)") (class "Default")
      (node (ref "LEDDRV1") (pin "9") (pinfunction "3A_9") (pintype "input"))
    )
    (net (code "118") (name "unconnected-(LEDDRV1-3Y-Pad10)") (class "Default")
      (node (ref "LEDDRV1") (pin "10") (pinfunction "3Y_10") (pintype "tri_state"))
    )
    (net (code "119") (name "unconnected-(LEDDRV1-3~{Z}-Pad11)") (class "Default")
      (node (ref "LEDDRV1") (pin "11") (pinfunction "3~{Z}_11") (pintype "tri_state"))
    )
    (net (code "120") (name "unconnected-(LEDDRV1-4A-Pad15)") (class "Default")
      (node (ref "LEDDRV1") (pin "15") (pinfunction "4A_15") (pintype "input"))
    )
    (net (code "121") (name "unconnected-(LEDDRV1-4Y-Pad14)") (class "Default")
      (node (ref "LEDDRV1") (pin "14") (pinfunction "4Y_14") (pintype "tri_state"))
    )
    (net (code "122") (name "unconnected-(LEDDRV1-4~{Z}-Pad13)") (class "Default")
      (node (ref "LEDDRV1") (pin "13") (pinfunction "4~{Z}_13") (pintype "tri_state"))
    )
    (net (code "123") (name "unconnected-(LEDDRV1-EN-Pad4)") (class "Default")
      (node (ref "LEDDRV1") (pin "4") (pinfunction "EN_4") (pintype "input"))
    )
    (net (code "124") (name "unconnected-(SC1-~{OSC}-Pad13)") (class "Default")
      (node (ref "SC1") (pin "13") (pinfunction "~{OSC}_13") (pintype "passive"))
    )
  )
)
